# G-MAS_SHIELD.net
KiCad netlist of a schematic drawn in EAGLE
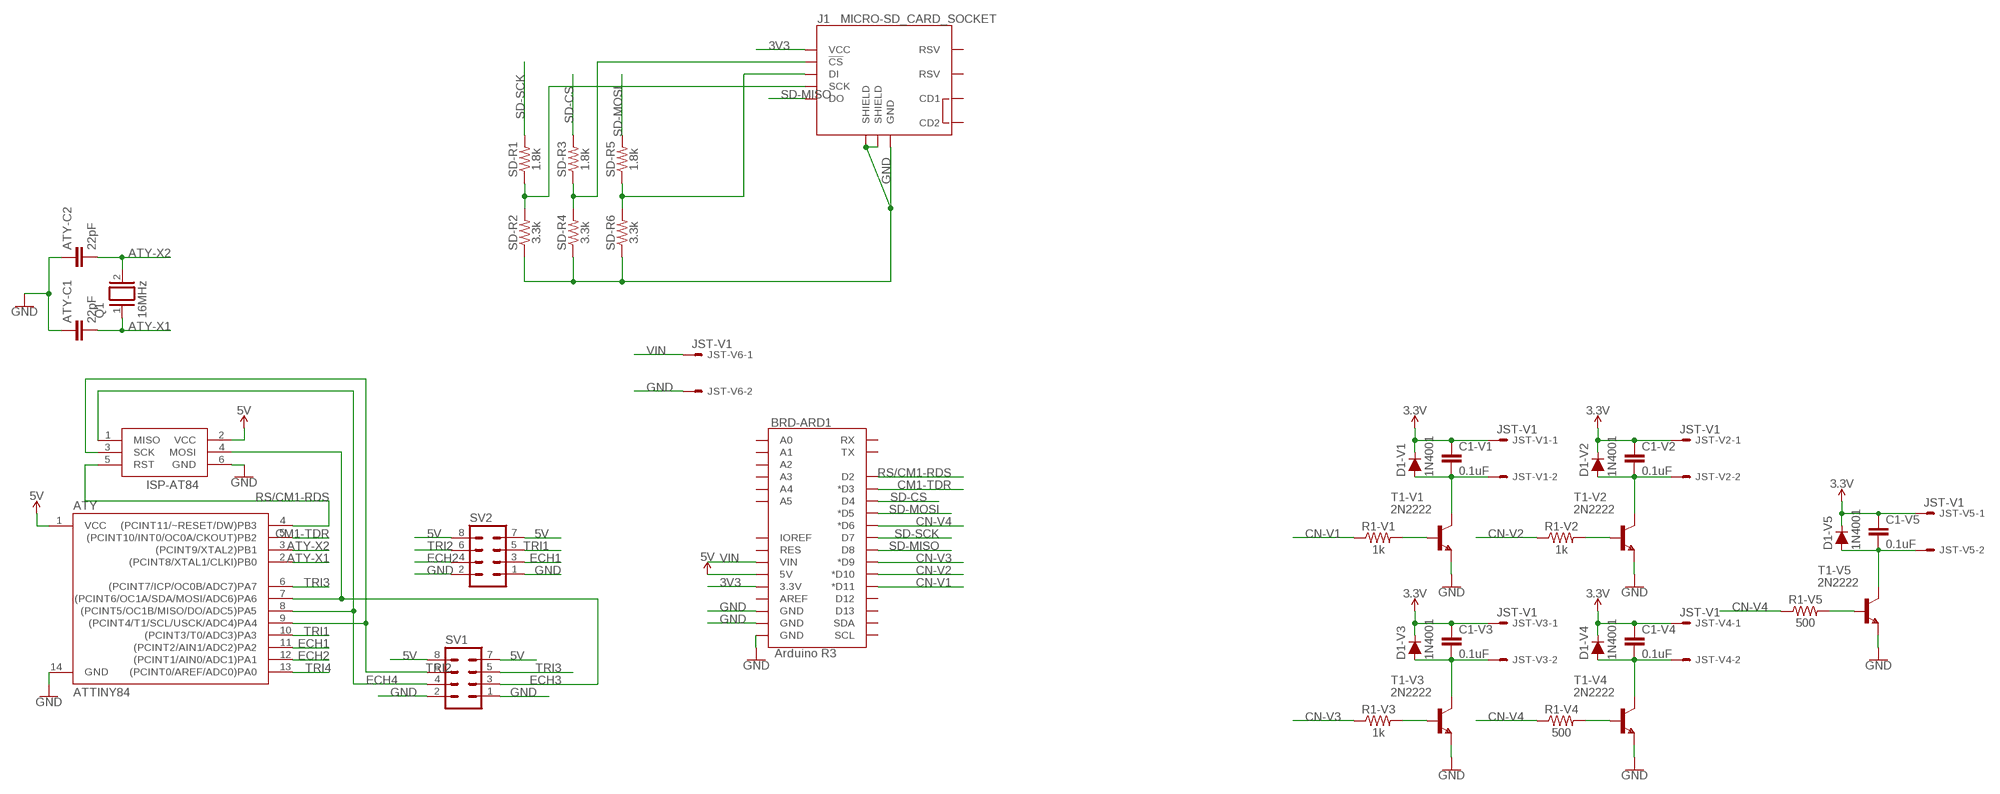
[diagram p0: schematic, sheet 1]

(export (version "E")
  (design (tool "Eeschema 10.0.6"))
  (components
    (comp (ref "ATY")
      (value "ATTINY84")
      (footprint "eagle-import:DIP14")
      (libsource (lib "eagle-import") (part "ATTINY84ATTINY84-20PU"))
    )
    (comp (ref "ATY-C1")
      (value "22pF")
      (footprint "eagle-import:CAP-PTH-SMALL-KIT")
      (libsource (lib "eagle-import") (part "0.1UF-KIT-EZ-50V-20%"))
    )
    (comp (ref "ATY-C2")
      (value "22pF")
      (footprint "eagle-import:CAP-PTH-SMALL-KIT")
      (libsource (lib "eagle-import") (part "0.1UF-KIT-EZ-50V-20%"))
    )
    (comp (ref "BRD-ARD1")
      (value "Arduino R3")
      (footprint "eagle-import:UNO_R3_SHIELD_NOLABELS")
      (libsource (lib "eagle-import") (part "ARDUINO_UNO_R3_SHIELDNOLABELS"))
    )
    (comp (ref "C1-V1")
      (value "0.1uF")
      (footprint "eagle-import:CAP-PTH-SMALL-KIT")
      (libsource (lib "eagle-import") (part "0.1UF-KIT-EZ-50V-20%"))
    )
    (comp (ref "C1-V2")
      (value "0.1uF")
      (footprint "eagle-import:CAP-PTH-SMALL-KIT")
      (libsource (lib "eagle-import") (part "0.1UF-KIT-EZ-50V-20%"))
    )
    (comp (ref "C1-V3")
      (value "0.1uF")
      (footprint "eagle-import:CAP-PTH-SMALL-KIT")
      (libsource (lib "eagle-import") (part "0.1UF-KIT-EZ-50V-20%"))
    )
    (comp (ref "C1-V4")
      (value "0.1uF")
      (footprint "eagle-import:CAP-PTH-SMALL-KIT")
      (libsource (lib "eagle-import") (part "0.1UF-KIT-EZ-50V-20%"))
    )
    (comp (ref "C1-V5")
      (value "0.1uF")
      (footprint "eagle-import:CAP-PTH-SMALL-KIT")
      (libsource (lib "eagle-import") (part "0.1UF-KIT-EZ-50V-20%"))
    )
    (comp (ref "D1-V1")
      (value "1N4001")
      (footprint "eagle-import:DIODE-1N4001")
      (libsource (lib "eagle-import") (part "DIODE-PTH"))
    )
    (comp (ref "D1-V2")
      (value "1N4001")
      (footprint "eagle-import:DIODE-1N4001")
      (libsource (lib "eagle-import") (part "DIODE-PTH"))
    )
    (comp (ref "D1-V3")
      (value "1N4001")
      (footprint "eagle-import:DIODE-1N4001")
      (libsource (lib "eagle-import") (part "DIODE-PTH"))
    )
    (comp (ref "D1-V4")
      (value "1N4001")
      (footprint "eagle-import:DIODE-1N4001")
      (libsource (lib "eagle-import") (part "DIODE-PTH"))
    )
    (comp (ref "D1-V5")
      (value "1N4001")
      (footprint "eagle-import:DIODE-1N4001")
      (libsource (lib "eagle-import") (part "DIODE-PTH"))
    )
    (comp (ref "ISP-AT84")
      (value "AVRISP-6")
      (footprint "eagle-import:AVRISP")
      (libsource (lib "eagle-import") (part "AVRISP-6"))
    )
    (comp (ref "J1")
      (value "MICRO-SD_CARD_SOCKET")
      (footprint "eagle-import:MICRO-SD-SOCKET")
      (libsource (lib "eagle-import") (part "MICRO-SD_CARD_SOCKET"))
    )
    (comp (ref "JST-V1")
      (value "JST-V1")
      (footprint "eagle-import:JST-XH-02-PACKAGE-LONG-PAD")
      (libsource (lib "eagle-import") (part "JST-XH-02-PIN-LONG-PAD"))
    )
    (comp (ref "JST-V2")
      (value "JST-V1")
      (footprint "eagle-import:JST-XH-02-PACKAGE-LONG-PAD")
      (libsource (lib "eagle-import") (part "JST-XH-02-PIN-LONG-PAD"))
    )
    (comp (ref "JST-V3")
      (value "JST-V1")
      (footprint "eagle-import:JST-XH-02-PACKAGE-LONG-PAD")
      (libsource (lib "eagle-import") (part "JST-XH-02-PIN-LONG-PAD"))
    )
    (comp (ref "JST-V4")
      (value "JST-V1")
      (footprint "eagle-import:JST-XH-02-PACKAGE-LONG-PAD")
      (libsource (lib "eagle-import") (part "JST-XH-02-PIN-LONG-PAD"))
    )
    (comp (ref "JST-V5")
      (value "JST-V1")
      (footprint "eagle-import:JST-XH-02-PACKAGE-LONG-PAD")
      (libsource (lib "eagle-import") (part "JST-XH-02-PIN-LONG-PAD"))
    )
    (comp (ref "JST-V6")
      (value "JST-V1")
      (footprint "eagle-import:JST-XH-02-PACKAGE-LONG-PAD")
      (libsource (lib "eagle-import") (part "JST-XH-02-PIN-LONG-PAD"))
    )
    (comp (ref "Q1")
      (value "16MHz")
      (footprint "eagle-import:QS")
      (libsource (lib "eagle-import") (part "XTAL/S"))
    )
    (comp (ref "R1-V1")
      (value "1k")
      (footprint "eagle-import:AXIAL-0.3")
      (libsource (lib "eagle-import") (part "1KOHM-HORIZ-1/4W-1%"))
    )
    (comp (ref "R1-V2")
      (value "1k")
      (footprint "eagle-import:AXIAL-0.3")
      (libsource (lib "eagle-import") (part "1KOHM-HORIZ-1/4W-1%"))
    )
    (comp (ref "R1-V3")
      (value "1k")
      (footprint "eagle-import:AXIAL-0.3")
      (libsource (lib "eagle-import") (part "1KOHM-HORIZ-1/4W-1%"))
    )
    (comp (ref "R1-V4")
      (value "500")
      (footprint "eagle-import:AXIAL-0.3")
      (libsource (lib "eagle-import") (part "1KOHM-HORIZ-1/4W-1%"))
    )
    (comp (ref "R1-V5")
      (value "500")
      (footprint "eagle-import:AXIAL-0.3")
      (libsource (lib "eagle-import") (part "1KOHM-HORIZ-1/4W-1%"))
    )
    (comp (ref "SD-R1")
      (value "1.8k")
      (footprint "eagle-import:0603")
      (libsource (lib "eagle-import") (part "1.8KOHM-0603-1/10W-1%"))
    )
    (comp (ref "SD-R2")
      (value "3.3k")
      (footprint "eagle-import:0603")
      (libsource (lib "eagle-import") (part "3.3KOHM-0603-1/10W-1%"))
    )
    (comp (ref "SD-R3")
      (value "1.8k")
      (footprint "eagle-import:0603")
      (libsource (lib "eagle-import") (part "1.8KOHM-0603-1/10W-1%"))
    )
    (comp (ref "SD-R4")
      (value "3.3k")
      (footprint "eagle-import:0603")
      (libsource (lib "eagle-import") (part "3.3KOHM-0603-1/10W-1%"))
    )
    (comp (ref "SD-R5")
      (value "1.8k")
      (footprint "eagle-import:0603")
      (libsource (lib "eagle-import") (part "1.8KOHM-0603-1/10W-1%"))
    )
    (comp (ref "SD-R6")
      (value "3.3k")
      (footprint "eagle-import:0603")
      (libsource (lib "eagle-import") (part "3.3KOHM-0603-1/10W-1%"))
    )
    (comp (ref "SV1")
      (value "MA04-2")
      (footprint "eagle-import:MA04-2")
      (libsource (lib "eagle-import") (part "MA04-2"))
    )
    (comp (ref "SV2")
      (value "MA04-2")
      (footprint "eagle-import:MA04-2")
      (libsource (lib "eagle-import") (part "MA04-2"))
    )
    (comp (ref "T1-V1")
      (value "2N2222")
      (footprint "eagle-import:TO92-EBC-OVAL")
      (libsource (lib "eagle-import") (part "2N2222"))
    )
    (comp (ref "T1-V2")
      (value "2N2222")
      (footprint "eagle-import:TO92-EBC-OVAL")
      (libsource (lib "eagle-import") (part "2N2222"))
    )
    (comp (ref "T1-V3")
      (value "2N2222")
      (footprint "eagle-import:TO92-EBC-OVAL")
      (libsource (lib "eagle-import") (part "2N2222"))
    )
    (comp (ref "T1-V4")
      (value "2N2222")
      (footprint "eagle-import:TO92-EBC-OVAL")
      (libsource (lib "eagle-import") (part "2N2222"))
    )
    (comp (ref "T1-V5")
      (value "2N2222")
      (footprint "eagle-import:TO92-EBC-OVAL")
      (libsource (lib "eagle-import") (part "2N2222"))
    )
  )
  (nets
    (net (code "1") (name "/3V3") (class "Default")
      (node (ref "BRD-ARD1") (pin "3.3V") (pinfunction "3.3V_3.3V") (pintype "bidirectional"))
      (node (ref "J1") (pin "VCC") (pinfunction "VCC_VCC") (pintype "bidirectional"))
    )
    (net (code "2") (name "/ATY-X1") (class "Default")
      (node (ref "ATY") (pin "2") (pinfunction "(PCINT8/XTAL1/CLKI)PB0_2") (pintype "bidirectional"))
      (node (ref "ATY-C1") (pin "2") (pinfunction "2_2") (pintype "passive"))
      (node (ref "Q1") (pin "1") (pinfunction "1_1") (pintype "passive"))
    )
    (net (code "3") (name "/ATY-X2") (class "Default")
      (node (ref "ATY") (pin "3") (pinfunction "(PCINT9/XTAL2)PB1_3") (pintype "bidirectional"))
      (node (ref "ATY-C2") (pin "2") (pinfunction "2_2") (pintype "passive"))
      (node (ref "Q1") (pin "2") (pinfunction "2_2") (pintype "passive"))
    )
    (net (code "4") (name "/CM1-TDR") (class "Default")
      (node (ref "ATY") (pin "5") (pinfunction "(PCINT10/INT0/OC0A/CKOUT)PB2_5") (pintype "bidirectional"))
      (node (ref "BRD-ARD1") (pin "D3") (pinfunction "*D3_D3") (pintype "bidirectional"))
    )
    (net (code "5") (name "/CN-V1") (class "Default")
      (node (ref "BRD-ARD1") (pin "D11") (pinfunction "*D11_D11") (pintype "bidirectional"))
      (node (ref "R1-V1") (pin "P$1") (pinfunction "1_P$1") (pintype "passive"))
    )
    (net (code "6") (name "/CN-V2") (class "Default")
      (node (ref "BRD-ARD1") (pin "D10") (pinfunction "*D10_D10") (pintype "bidirectional"))
      (node (ref "R1-V2") (pin "P$1") (pinfunction "1_P$1") (pintype "passive"))
    )
    (net (code "7") (name "/CN-V3") (class "Default")
      (node (ref "BRD-ARD1") (pin "D9") (pinfunction "*D9_D9") (pintype "bidirectional"))
      (node (ref "R1-V3") (pin "P$1") (pinfunction "1_P$1") (pintype "passive"))
    )
    (net (code "8") (name "/CN-V4") (class "Default")
      (node (ref "BRD-ARD1") (pin "D6") (pinfunction "*D6_D6") (pintype "bidirectional"))
      (node (ref "R1-V4") (pin "P$1") (pinfunction "1_P$1") (pintype "passive"))
      (node (ref "R1-V5") (pin "P$1") (pinfunction "1_P$1") (pintype "passive"))
    )
    (net (code "9") (name "/ECH1") (class "Default")
      (node (ref "ATY") (pin "11") (pinfunction "(PCINT2/AIN1/ADC2)PA2_11") (pintype "bidirectional"))
      (node (ref "SV2") (pin "3") (pinfunction "3_3") (pintype "passive"))
    )
    (net (code "10") (name "/ECH2") (class "Default")
      (node (ref "ATY") (pin "12") (pinfunction "(PCINT1/AIN0/ADC1)PA1_12") (pintype "bidirectional"))
      (node (ref "SV2") (pin "4") (pinfunction "4_4") (pintype "passive"))
    )
    (net (code "11") (name "/ECH3") (class "Default")
      (node (ref "ATY") (pin "7") (pinfunction "(PCINT6/OC1A/SDA/MOSI/ADC6)PA6_7") (pintype "bidirectional"))
      (node (ref "ISP-AT84") (pin "4") (pinfunction "MOSI_4") (pintype "output"))
      (node (ref "SV1") (pin "3") (pinfunction "3_3") (pintype "passive"))
    )
    (net (code "12") (name "/ECH4") (class "Default")
      (node (ref "ATY") (pin "8") (pinfunction "(PCINT5/OC1B/MISO/DO/ADC5)PA5_8") (pintype "bidirectional"))
      (node (ref "ISP-AT84") (pin "1") (pinfunction "MISO_1") (pintype "input"))
      (node (ref "SV1") (pin "4") (pinfunction "4_4") (pintype "passive"))
    )
    (net (code "13") (name "/RS{slash}CM1-RDS") (class "Default")
      (node (ref "ATY") (pin "4") (pinfunction "(PCINT11/~{RESET/DW})PB3_4") (pintype "bidirectional"))
      (node (ref "BRD-ARD1") (pin "D2") (pinfunction "D2_D2") (pintype "bidirectional"))
      (node (ref "ISP-AT84") (pin "5") (pinfunction "RST_5") (pintype "output"))
    )
    (net (code "14") (name "/SD-CS") (class "Default")
      (node (ref "BRD-ARD1") (pin "D4") (pinfunction "D4_D4") (pintype "bidirectional"))
      (node (ref "SD-R3") (pin "2") (pinfunction "2_2") (pintype "passive"))
    )
    (net (code "15") (name "/SD-MISO") (class "Default")
      (node (ref "BRD-ARD1") (pin "D8") (pinfunction "D8_D8") (pintype "bidirectional"))
      (node (ref "J1") (pin "DO") (pinfunction "DO_DO") (pintype "bidirectional"))
    )
    (net (code "16") (name "/SD-MOSI") (class "Default")
      (node (ref "BRD-ARD1") (pin "D5") (pinfunction "*D5_D5") (pintype "bidirectional"))
      (node (ref "SD-R5") (pin "2") (pinfunction "2_2") (pintype "passive"))
    )
    (net (code "17") (name "/SD-SCK") (class "Default")
      (node (ref "BRD-ARD1") (pin "D7") (pinfunction "D7_D7") (pintype "bidirectional"))
      (node (ref "SD-R1") (pin "2") (pinfunction "2_2") (pintype "passive"))
    )
    (net (code "18") (name "/TRI1") (class "Default")
      (node (ref "ATY") (pin "10") (pinfunction "(PCINT3/T0/ADC3)PA3_10") (pintype "bidirectional"))
      (node (ref "SV2") (pin "5") (pinfunction "5_5") (pintype "passive"))
    )
    (net (code "19") (name "/TRI2") (class "Default")
      (node (ref "ATY") (pin "13") (pinfunction "(PCINT0/AREF/ADC0)PA0_13") (pintype "bidirectional"))
      (node (ref "SV2") (pin "6") (pinfunction "6_6") (pintype "passive"))
    )
    (net (code "20") (name "/TRI3") (class "Default")
      (node (ref "ATY") (pin "6") (pinfunction "(PCINT7/ICP/OC0B/ADC7)PA7_6") (pintype "bidirectional"))
      (node (ref "SV1") (pin "5") (pinfunction "5_5") (pintype "passive"))
    )
    (net (code "21") (name "/TRI4") (class "Default")
      (node (ref "ATY") (pin "9") (pinfunction "(PCINT4/T1/SCL/USCK/ADC4)PA4_9") (pintype "bidirectional"))
      (node (ref "ISP-AT84") (pin "3") (pinfunction "SCK_3") (pintype "output"))
      (node (ref "SV1") (pin "6") (pinfunction "6_6") (pintype "passive"))
    )
    (net (code "22") (name "/VIN") (class "Default")
      (node (ref "BRD-ARD1") (pin "VIN") (pinfunction "VIN_VIN") (pintype "bidirectional"))
      (node (ref "JST-V6") (pin "1") (pinfunction "S_1") (pintype "passive"))
    )
    (net (code "23") (name "3.3V") (class "Default")
      (node (ref "C1-V1") (pin "1") (pinfunction "1_1") (pintype "passive"))
      (node (ref "C1-V2") (pin "1") (pinfunction "1_1") (pintype "passive"))
      (node (ref "C1-V3") (pin "1") (pinfunction "1_1") (pintype "passive"))
      (node (ref "C1-V4") (pin "1") (pinfunction "1_1") (pintype "passive"))
      (node (ref "C1-V5") (pin "1") (pinfunction "1_1") (pintype "passive"))
      (node (ref "D1-V1") (pin "C") (pinfunction "C_C") (pintype "passive"))
      (node (ref "D1-V2") (pin "C") (pinfunction "C_C") (pintype "passive"))
      (node (ref "D1-V3") (pin "C") (pinfunction "C_C") (pintype "passive"))
      (node (ref "D1-V4") (pin "C") (pinfunction "C_C") (pintype "passive"))
      (node (ref "D1-V5") (pin "C") (pinfunction "C_C") (pintype "passive"))
      (node (ref "JST-V1") (pin "1") (pinfunction "S_1") (pintype "passive"))
      (node (ref "JST-V2") (pin "1") (pinfunction "S_1") (pintype "passive"))
      (node (ref "JST-V3") (pin "1") (pinfunction "S_1") (pintype "passive"))
      (node (ref "JST-V4") (pin "1") (pinfunction "S_1") (pintype "passive"))
      (node (ref "JST-V5") (pin "1") (pinfunction "S_1") (pintype "passive"))
    )
    (net (code "24") (name "5V") (class "Default")
      (node (ref "ATY") (pin "1") (pinfunction "VCC_1") (pintype "bidirectional"))
      (node (ref "BRD-ARD1") (pin "5V") (pinfunction "5V_5V") (pintype "bidirectional"))
      (node (ref "ISP-AT84") (pin "2") (pinfunction "VCC_2") (pintype "power_in"))
      (node (ref "SV1") (pin "7") (pinfunction "7_7") (pintype "passive"))
      (node (ref "SV1") (pin "8") (pinfunction "8_8") (pintype "passive"))
      (node (ref "SV2") (pin "7") (pinfunction "7_7") (pintype "passive"))
      (node (ref "SV2") (pin "8") (pinfunction "8_8") (pintype "passive"))
    )
    (net (code "25") (name "GND") (class "Default")
      (node (ref "ATY") (pin "14") (pinfunction "GND_14") (pintype "bidirectional"))
      (node (ref "ATY-C1") (pin "1") (pinfunction "1_1") (pintype "passive"))
      (node (ref "ATY-C2") (pin "1") (pinfunction "1_1") (pintype "passive"))
      (node (ref "BRD-ARD1") (pin "GND@0") (pinfunction "GND_GND@0") (pintype "bidirectional"))
      (node (ref "BRD-ARD1") (pin "GND@1") (pinfunction "GND_GND@1") (pintype "bidirectional"))
      (node (ref "BRD-ARD1") (pin "GND@2") (pinfunction "GND_GND@2") (pintype "bidirectional"))
      (node (ref "ISP-AT84") (pin "6") (pinfunction "GND_6") (pintype "power_in"))
      (node (ref "J1") (pin "GND") (pinfunction "GND_GND") (pintype "bidirectional"))
      (node (ref "J1") (pin "GND1") (pinfunction "SHIELD_GND1") (pintype "bidirectional"))
      (node (ref "J1") (pin "GND3") (pinfunction "SHIELD_GND3") (pintype "bidirectional"))
      (node (ref "JST-V6") (pin "2") (pinfunction "S_2") (pintype "passive"))
      (node (ref "SD-R2") (pin "1") (pinfunction "1_1") (pintype "passive"))
      (node (ref "SD-R4") (pin "1") (pinfunction "1_1") (pintype "passive"))
      (node (ref "SD-R6") (pin "1") (pinfunction "1_1") (pintype "passive"))
      (node (ref "SV1") (pin "1") (pinfunction "1_1") (pintype "passive"))
      (node (ref "SV1") (pin "2") (pinfunction "2_2") (pintype "passive"))
      (node (ref "SV2") (pin "1") (pinfunction "1_1") (pintype "passive"))
      (node (ref "SV2") (pin "2") (pinfunction "2_2") (pintype "passive"))
      (node (ref "T1-V1") (pin "E") (pinfunction "E_E") (pintype "passive"))
      (node (ref "T1-V2") (pin "E") (pinfunction "E_E") (pintype "passive"))
      (node (ref "T1-V3") (pin "E") (pinfunction "E_E") (pintype "passive"))
      (node (ref "T1-V4") (pin "E") (pinfunction "E_E") (pintype "passive"))
      (node (ref "T1-V5") (pin "E") (pinfunction "E_E") (pintype "passive"))
    )
    (net (code "26") (name "Net-(J1-PadDI)") (class "Default")
      (node (ref "J1") (pin "DI") (pinfunction "DI_DI") (pintype "bidirectional"))
      (node (ref "SD-R5") (pin "1") (pinfunction "1_1") (pintype "passive"))
      (node (ref "SD-R6") (pin "2") (pinfunction "2_2") (pintype "passive"))
    )
    (net (code "27") (name "Net-(J1-SCK)") (class "Default")
      (node (ref "J1") (pin "SCLK") (pinfunction "SCK_SCLK") (pintype "bidirectional"))
      (node (ref "SD-R1") (pin "1") (pinfunction "1_1") (pintype "passive"))
      (node (ref "SD-R2") (pin "2") (pinfunction "2_2") (pintype "passive"))
    )
    (net (code "28") (name "Net-(J1-~{CS})") (class "Default")
      (node (ref "J1") (pin "CS") (pinfunction "~{CS}_CS") (pintype "bidirectional"))
      (node (ref "SD-R3") (pin "1") (pinfunction "1_1") (pintype "passive"))
      (node (ref "SD-R4") (pin "2") (pinfunction "2_2") (pintype "passive"))
    )
    (net (code "29") (name "Net-(JST-V1B-S)") (class "Default")
      (node (ref "C1-V1") (pin "2") (pinfunction "2_2") (pintype "passive"))
      (node (ref "D1-V1") (pin "A") (pinfunction "A_A") (pintype "passive"))
      (node (ref "JST-V1") (pin "2") (pinfunction "S_2") (pintype "passive"))
      (node (ref "T1-V1") (pin "C") (pinfunction "C_C") (pintype "passive"))
    )
    (net (code "30") (name "Net-(JST-V2B-S)") (class "Default")
      (node (ref "C1-V2") (pin "2") (pinfunction "2_2") (pintype "passive"))
      (node (ref "D1-V2") (pin "A") (pinfunction "A_A") (pintype "passive"))
      (node (ref "JST-V2") (pin "2") (pinfunction "S_2") (pintype "passive"))
      (node (ref "T1-V2") (pin "C") (pinfunction "C_C") (pintype "passive"))
    )
    (net (code "31") (name "Net-(JST-V3B-S)") (class "Default")
      (node (ref "C1-V3") (pin "2") (pinfunction "2_2") (pintype "passive"))
      (node (ref "D1-V3") (pin "A") (pinfunction "A_A") (pintype "passive"))
      (node (ref "JST-V3") (pin "2") (pinfunction "S_2") (pintype "passive"))
      (node (ref "T1-V3") (pin "C") (pinfunction "C_C") (pintype "passive"))
    )
    (net (code "32") (name "Net-(JST-V4B-S)") (class "Default")
      (node (ref "C1-V4") (pin "2") (pinfunction "2_2") (pintype "passive"))
      (node (ref "D1-V4") (pin "A") (pinfunction "A_A") (pintype "passive"))
      (node (ref "JST-V4") (pin "2") (pinfunction "S_2") (pintype "passive"))
      (node (ref "T1-V4") (pin "C") (pinfunction "C_C") (pintype "passive"))
    )
    (net (code "33") (name "Net-(JST-V5B-S)") (class "Default")
      (node (ref "C1-V5") (pin "2") (pinfunction "2_2") (pintype "passive"))
      (node (ref "D1-V5") (pin "A") (pinfunction "A_A") (pintype "passive"))
      (node (ref "JST-V5") (pin "2") (pinfunction "S_2") (pintype "passive"))
      (node (ref "T1-V5") (pin "C") (pinfunction "C_C") (pintype "passive"))
    )
    (net (code "34") (name "Net-(R1-V1-2)") (class "Default")
      (node (ref "R1-V1") (pin "P$2") (pinfunction "2_P$2") (pintype "passive"))
      (node (ref "T1-V1") (pin "B") (pinfunction "B_B") (pintype "passive"))
    )
    (net (code "35") (name "Net-(R1-V2-2)") (class "Default")
      (node (ref "R1-V2") (pin "P$2") (pinfunction "2_P$2") (pintype "passive"))
      (node (ref "T1-V2") (pin "B") (pinfunction "B_B") (pintype "passive"))
    )
    (net (code "36") (name "Net-(R1-V3-2)") (class "Default")
      (node (ref "R1-V3") (pin "P$2") (pinfunction "2_P$2") (pintype "passive"))
      (node (ref "T1-V3") (pin "B") (pinfunction "B_B") (pintype "passive"))
    )
    (net (code "37") (name "Net-(R1-V4-2)") (class "Default")
      (node (ref "R1-V4") (pin "P$2") (pinfunction "2_P$2") (pintype "passive"))
      (node (ref "T1-V4") (pin "B") (pinfunction "B_B") (pintype "passive"))
    )
    (net (code "38") (name "Net-(R1-V5-2)") (class "Default")
      (node (ref "R1-V5") (pin "P$2") (pinfunction "2_P$2") (pintype "passive"))
      (node (ref "T1-V5") (pin "B") (pinfunction "B_B") (pintype "passive"))
    )
    (net (code "39") (name "unconnected-(BRD-ARD1-PadA0)") (class "Default")
      (node (ref "BRD-ARD1") (pin "A0") (pinfunction "A0_A0") (pintype "bidirectional"))
    )
    (net (code "40") (name "unconnected-(BRD-ARD1-PadA1)") (class "Default")
      (node (ref "BRD-ARD1") (pin "A1") (pinfunction "A1_A1") (pintype "bidirectional"))
    )
    (net (code "41") (name "unconnected-(BRD-ARD1-PadA2)") (class "Default")
      (node (ref "BRD-ARD1") (pin "A2") (pinfunction "A2_A2") (pintype "bidirectional"))
    )
    (net (code "42") (name "unconnected-(BRD-ARD1-PadA3)") (class "Default")
      (node (ref "BRD-ARD1") (pin "A3") (pinfunction "A3_A3") (pintype "bidirectional"))
    )
    (net (code "43") (name "unconnected-(BRD-ARD1-PadA4)") (class "Default")
      (node (ref "BRD-ARD1") (pin "A4") (pinfunction "A4_A4") (pintype "bidirectional"))
    )
    (net (code "44") (name "unconnected-(BRD-ARD1-PadA5)") (class "Default")
      (node (ref "BRD-ARD1") (pin "A5") (pinfunction "A5_A5") (pintype "bidirectional"))
    )
    (net (code "45") (name "unconnected-(BRD-ARD1-PadAREF)") (class "Default")
      (node (ref "BRD-ARD1") (pin "AREF") (pinfunction "AREF_AREF") (pintype "bidirectional"))
    )
    (net (code "46") (name "unconnected-(BRD-ARD1-PadD12)") (class "Default")
      (node (ref "BRD-ARD1") (pin "D12") (pinfunction "D12_D12") (pintype "bidirectional"))
    )
    (net (code "47") (name "unconnected-(BRD-ARD1-PadD13)") (class "Default")
      (node (ref "BRD-ARD1") (pin "D13") (pinfunction "D13_D13") (pintype "bidirectional"))
    )
    (net (code "48") (name "unconnected-(BRD-ARD1-PadIOREF)") (class "Default")
      (node (ref "BRD-ARD1") (pin "IOREF") (pinfunction "IOREF_IOREF") (pintype "bidirectional"))
    )
    (net (code "49") (name "unconnected-(BRD-ARD1-PadRES)") (class "Default")
      (node (ref "BRD-ARD1") (pin "RES") (pinfunction "RES_RES") (pintype "bidirectional"))
    )
    (net (code "50") (name "unconnected-(BRD-ARD1-PadRX)") (class "Default")
      (node (ref "BRD-ARD1") (pin "RX") (pinfunction "RX_RX") (pintype "bidirectional"))
    )
    (net (code "51") (name "unconnected-(BRD-ARD1-PadSCL)") (class "Default")
      (node (ref "BRD-ARD1") (pin "SCL") (pinfunction "SCL_SCL") (pintype "bidirectional"))
    )
    (net (code "52") (name "unconnected-(BRD-ARD1-PadSDA)") (class "Default")
      (node (ref "BRD-ARD1") (pin "SDA") (pinfunction "SDA_SDA") (pintype "bidirectional"))
    )
    (net (code "53") (name "unconnected-(BRD-ARD1-PadTX)") (class "Default")
      (node (ref "BRD-ARD1") (pin "TX") (pinfunction "TX_TX") (pintype "bidirectional"))
    )
    (net (code "54") (name "unconnected-(J1-PadCD1)") (class "Default")
      (node (ref "J1") (pin "CD1") (pinfunction "CD1_CD1") (pintype "bidirectional"))
    )
    (net (code "55") (name "unconnected-(J1-PadCD2)") (class "Default")
      (node (ref "J1") (pin "CD2") (pinfunction "CD2_CD2") (pintype "bidirectional"))
    )
    (net (code "56") (name "unconnected-(J1-RSV-PadRSV1)") (class "Default")
      (node (ref "J1") (pin "RSV1") (pinfunction "RSV_RSV1") (pintype "bidirectional"))
    )
    (net (code "57") (name "unconnected-(J1-RSV-PadRSV2)") (class "Default")
      (node (ref "J1") (pin "RSV2") (pinfunction "RSV_RSV2") (pintype "bidirectional"))
    )
  )
)
